# Sensors.net
KiCad netlist of a schematic drawn in Altium Designer
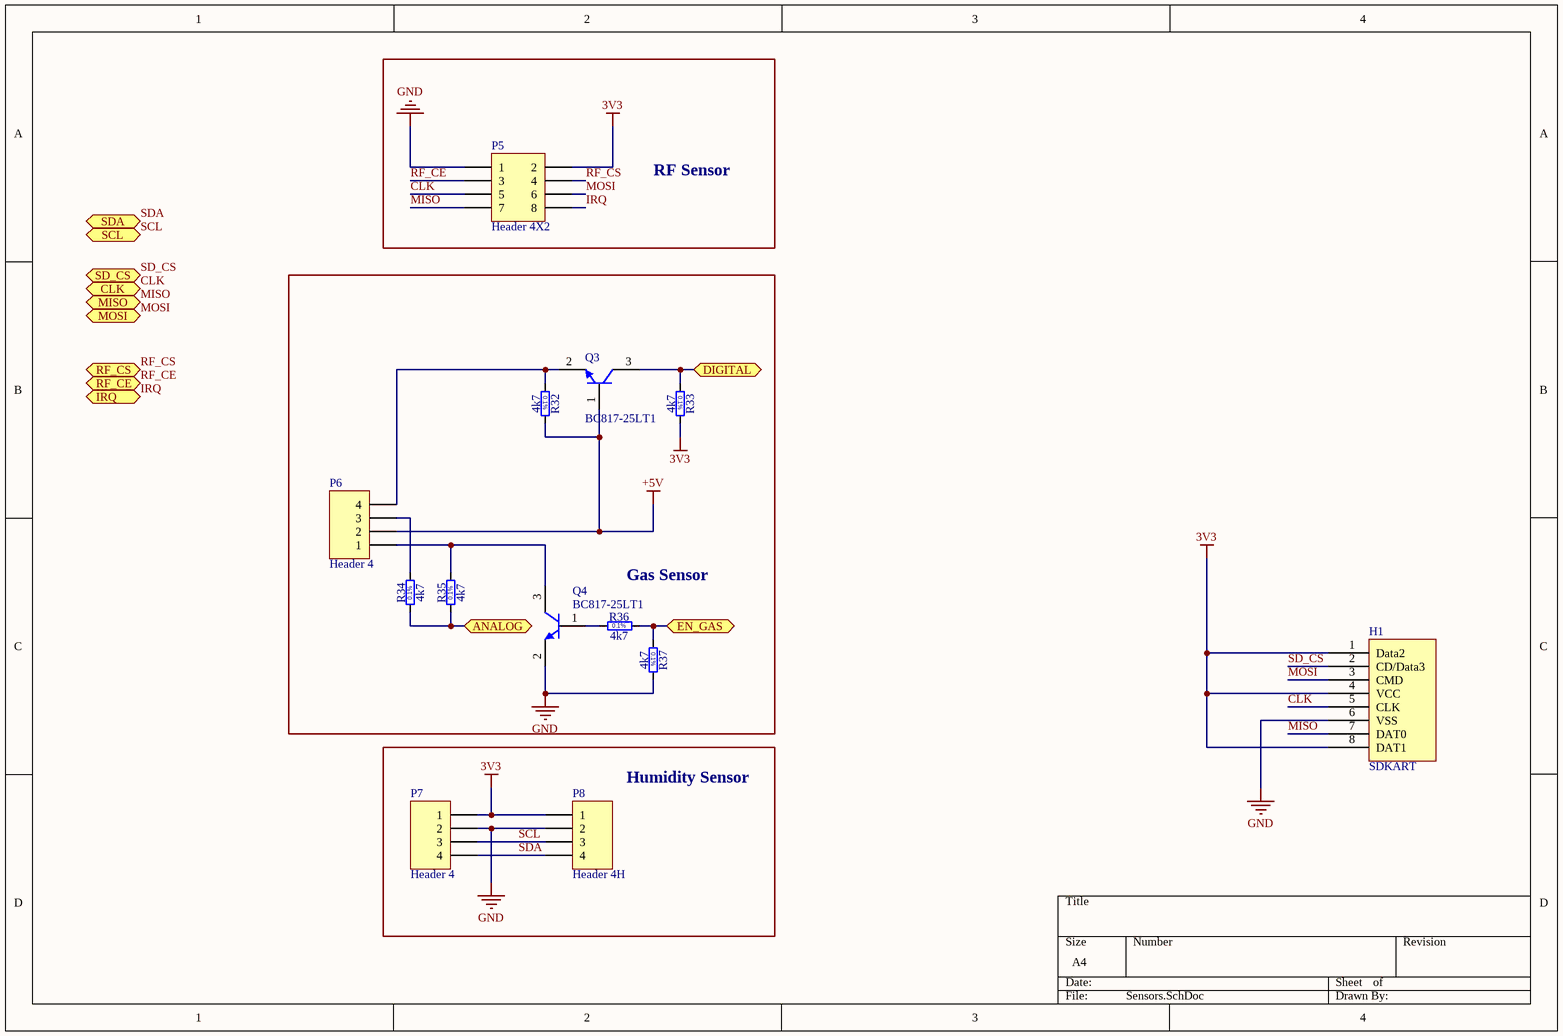
[diagram p0: Sensors.SchDoc]

(export (version "E")
  (design (tool "Eeschema 10.0.6"))
  (components
    (comp (ref "H1")
      (value "SDKART")
      (footprint "PCBComponent_1")
      (libsource (lib "Integrated_Library") (part "SDKART"))
    )
    (comp (ref "P5")
      (value "Header 4X2")
      (footprint "HDR2X4")
      (description "Header, 4-Pin, Dual row")
      (fields (field (name "PUBLISHER") "Altium Limited"))
      (libsource (lib "Miscellaneous Connectors") (part "Header 4X2"))
    )
    (comp (ref "P6")
      (value "Header 4")
      (footprint "HDR1X4")
      (description "Header, 4-Pin")
      (fields (field (name "PUBLISHER") "Altium Limited"))
      (libsource (lib "") (part "Header 4_1"))
    )
    (comp (ref "P7")
      (value "Header 4")
      (footprint "HDR1X4")
      (description "Header, 4-Pin")
      (fields (field (name "PUBLISHER") "Altium Limited"))
      (libsource (lib "Miscellaneous Connectors") (part "Header 4"))
    )
    (comp (ref "P8")
      (value "Header 4H")
      (footprint "HDR1X4H")
      (description "Header, 4-Pin, Right Angle")
      (fields (field (name "PUBLISHER") "Altium Limited"))
      (libsource (lib "Miscellaneous Connectors") (part "Header 4H"))
    )
    (comp (ref "Q3")
      (value "BC817-25LT1")
      (footprint "ONSC-SOT-23-3-318-08_V")
      (description "General Purpose Transistor, NPN Silicon, 3-Pin SOT-23, Tape and Reel")
      (fields (field (name "MANUFACTURER") "On Semiconductor"))
      (libsource (lib "ON Semi General Purpose Transistors") (part "BC817-25LT1"))
    )
    (comp (ref "Q4")
      (value "BC817-25LT1")
      (footprint "ONSC-SOT-23-3-318-08_V")
      (description "General Purpose Transistor, NPN Silicon, 3-Pin SOT-23, Tape and Reel")
      (fields (field (name "MANUFACTURER") "On Semiconductor"))
      (libsource (lib "ON Semi General Purpose Transistors") (part "BC817-25LT1"))
    )
    (comp (ref "R32")
      (value "4k7")
      (footprint "RESC2012X60N")
      (description "Resistor - 0.1%")
      (fields
        (field (name "PART NUMBER") "R0805_1K1_0.1%_0.1W_10PPM")
        (field (name "POWER") "0.1W")
        (field (name "AUTHOR") "CERN DEM JLC")
      )
      (libsource (lib "Resistors") (part "Resistor - 0.1%"))
    )
    (comp (ref "R33")
      (value "4k7")
      (footprint "RESC2012X60N")
      (description "Resistor - 0.1%")
      (fields
        (field (name "PART NUMBER") "R0805_1K1_0.1%_0.1W_10PPM")
        (field (name "POWER") "0.1W")
        (field (name "AUTHOR") "CERN DEM JLC")
      )
      (libsource (lib "Resistors") (part "Resistor - 0.1%"))
    )
    (comp (ref "R34")
      (value "4k7")
      (footprint "RESC2012X60N")
      (description "Resistor - 0.1%")
      (fields
        (field (name "PART NUMBER") "R0805_1K1_0.1%_0.1W_10PPM")
        (field (name "POWER") "0.1W")
        (field (name "AUTHOR") "CERN DEM JLC")
      )
      (libsource (lib "Resistors") (part "Resistor - 0.1%"))
    )
    (comp (ref "R35")
      (value "4k7")
      (footprint "RESC2012X60N")
      (description "Resistor - 0.1%")
      (fields
        (field (name "PART NUMBER") "R0805_1K1_0.1%_0.1W_10PPM")
        (field (name "POWER") "0.1W")
        (field (name "AUTHOR") "CERN DEM JLC")
      )
      (libsource (lib "Resistors") (part "Resistor - 0.1%"))
    )
    (comp (ref "R36")
      (value "4k7")
      (footprint "RESC2012X60N")
      (description "Resistor - 0.1%")
      (fields
        (field (name "PART NUMBER") "R0805_1K1_0.1%_0.1W_10PPM")
        (field (name "POWER") "0.1W")
        (field (name "AUTHOR") "CERN DEM JLC")
      )
      (libsource (lib "Resistors") (part "Resistor - 0.1%"))
    )
    (comp (ref "R37")
      (value "4k7")
      (footprint "RESC2012X60N")
      (description "Resistor - 0.1%")
      (fields
        (field (name "PART NUMBER") "R0805_1K1_0.1%_0.1W_10PPM")
        (field (name "POWER") "0.1W")
        (field (name "AUTHOR") "CERN DEM JLC")
      )
      (libsource (lib "Resistors") (part "Resistor - 0.1%"))
    )
  )
  (nets
    (net (code "1") (name "+5V") (class "Default")
      (node (ref "P6") (pin "2") (pinfunction "2_2") (pintype "passive"))
      (node (ref "Q3") (pin "1") (pinfunction "B_1") (pintype "passive"))
      (node (ref "R32") (pin "2") (pinfunction "2_2") (pintype "passive"))
    )
    (net (code "2") (name "/ANALOG") (class "Default")
      (node (ref "R34") (pin "1") (pinfunction "1_1") (pintype "passive"))
      (node (ref "R35") (pin "1") (pinfunction "1_1") (pintype "passive"))
    )
    (net (code "3") (name "/CLK") (class "Default")
      (node (ref "H1") (pin "5") (pinfunction "CLK_5") (pintype "passive"))
      (node (ref "P5") (pin "5") (pinfunction "5_5") (pintype "passive"))
    )
    (net (code "4") (name "/DIGITAL") (class "Default")
      (node (ref "Q3") (pin "3") (pinfunction "C_3") (pintype "passive"))
      (node (ref "R33") (pin "1") (pinfunction "1_1") (pintype "passive"))
    )
    (net (code "5") (name "/EN_GAS") (class "Default")
      (node (ref "R36") (pin "2") (pinfunction "2_2") (pintype "passive"))
      (node (ref "R37") (pin "1") (pinfunction "1_1") (pintype "passive"))
    )
    (net (code "6") (name "/IRQ") (class "Default")
      (node (ref "P5") (pin "8") (pinfunction "8_8") (pintype "passive"))
    )
    (net (code "7") (name "/MISO") (class "Default")
      (node (ref "H1") (pin "7") (pinfunction "DAT0_7") (pintype "passive"))
      (node (ref "P5") (pin "7") (pinfunction "7_7") (pintype "passive"))
    )
    (net (code "8") (name "/MOSI") (class "Default")
      (node (ref "H1") (pin "3") (pinfunction "CMD_3") (pintype "passive"))
      (node (ref "P5") (pin "6") (pinfunction "6_6") (pintype "passive"))
    )
    (net (code "9") (name "/RF_CE") (class "Default")
      (node (ref "P5") (pin "3") (pinfunction "3_3") (pintype "passive"))
    )
    (net (code "10") (name "/RF_CS") (class "Default")
      (node (ref "P5") (pin "4") (pinfunction "4_4") (pintype "passive"))
    )
    (net (code "11") (name "/SCL") (class "Default")
      (node (ref "P7") (pin "3") (pinfunction "3_3") (pintype "passive"))
      (node (ref "P8") (pin "3") (pinfunction "3_3") (pintype "passive"))
    )
    (net (code "12") (name "/SDA") (class "Default")
      (node (ref "P7") (pin "4") (pinfunction "4_4") (pintype "passive"))
      (node (ref "P8") (pin "4") (pinfunction "4_4") (pintype "passive"))
    )
    (net (code "13") (name "/SD_CS") (class "Default")
      (node (ref "H1") (pin "2") (pinfunction "CD/Data3_2") (pintype "passive"))
    )
    (net (code "14") (name "3V3") (class "Default")
      (node (ref "H1") (pin "1") (pinfunction "Data2_1") (pintype "passive"))
      (node (ref "H1") (pin "4") (pinfunction "VCC_4") (pintype "passive"))
      (node (ref "H1") (pin "8") (pinfunction "DAT1_8") (pintype "passive"))
      (node (ref "P5") (pin "2") (pinfunction "2_2") (pintype "passive"))
      (node (ref "P7") (pin "1") (pinfunction "1_1") (pintype "passive"))
      (node (ref "P8") (pin "1") (pinfunction "1_1") (pintype "passive"))
      (node (ref "R33") (pin "2") (pinfunction "2_2") (pintype "passive"))
    )
    (net (code "15") (name "GND") (class "Default")
      (node (ref "H1") (pin "6") (pinfunction "VSS_6") (pintype "passive"))
      (node (ref "P5") (pin "1") (pinfunction "1_1") (pintype "passive"))
      (node (ref "P7") (pin "2") (pinfunction "2_2") (pintype "passive"))
      (node (ref "P8") (pin "2") (pinfunction "2_2") (pintype "passive"))
      (node (ref "Q4") (pin "2") (pinfunction "E_2") (pintype "passive"))
      (node (ref "R37") (pin "2") (pinfunction "2_2") (pintype "passive"))
    )
    (net (code "16") (name "Net-(P6-Pad3)") (class "Default")
      (node (ref "P6") (pin "3") (pinfunction "3_3") (pintype "passive"))
      (node (ref "R34") (pin "2") (pinfunction "2_2") (pintype "passive"))
    )
    (net (code "17") (name "Net-(Q3-E)") (class "Default")
      (node (ref "P6") (pin "4") (pinfunction "4_4") (pintype "passive"))
      (node (ref "Q3") (pin "2") (pinfunction "E_2") (pintype "passive"))
      (node (ref "R32") (pin "1") (pinfunction "1_1") (pintype "passive"))
    )
    (net (code "18") (name "Net-(Q4-B)") (class "Default")
      (node (ref "Q4") (pin "1") (pinfunction "B_1") (pintype "passive"))
      (node (ref "R36") (pin "1") (pinfunction "1_1") (pintype "passive"))
    )
    (net (code "19") (name "Net-(Q4-C)") (class "Default")
      (node (ref "P6") (pin "1") (pinfunction "1_1") (pintype "passive"))
      (node (ref "Q4") (pin "3") (pinfunction "C_3") (pintype "passive"))
      (node (ref "R35") (pin "2") (pinfunction "2_2") (pintype "passive"))
    )
  )
)
